# laser-jog-controller-0.net
KiCad netlist of a schematic drawn in EAGLE
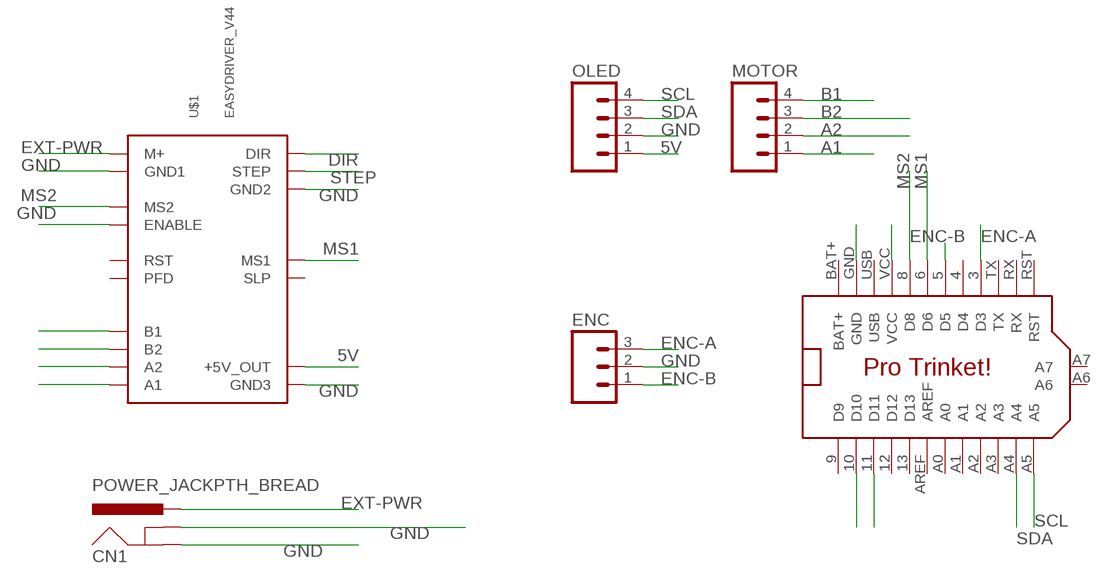
[diagram p0: schematic, sheet 1]

(export (version "E")
  (design (tool "Eeschema 10.0.6"))
  (components
    (comp (ref "CN1")
      (value "POWER_JACKPTH_BREAD")
      (footprint "eagle-import:POWER_JACK_PTH_BREAD")
      (libsource (lib "eagle-import") (part "POWER_JACKPTH_BREAD"))
    )
    (comp (ref "ENC")
      (value "M03LOCK_LONGPADS")
      (footprint "eagle-import:1X03_LOCK_LONGPADS")
      (libsource (lib "eagle-import") (part "M03LOCK_LONGPADS"))
    )
    (comp (ref "MOTOR")
      (value "M04LOCK_LONGPADS")
      (footprint "eagle-import:1X04_LOCK_LONGPADS")
      (libsource (lib "eagle-import") (part "M04LOCK_LONGPADS"))
    )
    (comp (ref "OLED")
      (value "M04LOCK_LONGPADS")
      (footprint "eagle-import:1X04_LOCK_LONGPADS")
      (libsource (lib "eagle-import") (part "M04LOCK_LONGPADS"))
    )
    (comp (ref "U$1")
      (value "EASYDRIVER_V44")
      (footprint "eagle-import:EASYDRIVER_V44")
      (libsource (lib "eagle-import") (part "EASYDRIVER_V44"))
    )
    (comp (ref "U$2")
      (value "PRO_TRINKET")
      (footprint "eagle-import:PROTRINKET")
      (libsource (lib "eagle-import") (part "PRO_TRINKET"))
    )
  )
  (nets
    (net (code "1") (name "/5V") (class "Default")
      (node (ref "OLED") (pin "1") (pinfunction "1_1") (pintype "passive"))
      (node (ref "U$1") (pin "P$11") (pinfunction "+5V_OUT_P$11") (pintype "bidirectional"))
      (node (ref "U$2") (pin "VCC") (pinfunction "VCC_VCC") (pintype "power_in"))
    )
    (net (code "2") (name "/A1") (class "Default")
      (node (ref "MOTOR") (pin "1") (pinfunction "1_1") (pintype "passive"))
      (node (ref "U$1") (pin "A1") (pinfunction "A1_A1") (pintype "bidirectional"))
    )
    (net (code "3") (name "/A2") (class "Default")
      (node (ref "MOTOR") (pin "2") (pinfunction "2_2") (pintype "passive"))
      (node (ref "U$1") (pin "A2") (pinfunction "A2_A2") (pintype "bidirectional"))
    )
    (net (code "4") (name "/B1") (class "Default")
      (node (ref "MOTOR") (pin "4") (pinfunction "4_4") (pintype "passive"))
      (node (ref "U$1") (pin "B1") (pinfunction "B1_B1") (pintype "bidirectional"))
    )
    (net (code "5") (name "/B2") (class "Default")
      (node (ref "MOTOR") (pin "3") (pinfunction "3_3") (pintype "passive"))
      (node (ref "U$1") (pin "B2") (pinfunction "B2_B2") (pintype "bidirectional"))
    )
    (net (code "6") (name "/BAT+") (class "Default")
      (node (ref "U$2") (pin "BAT+") (pinfunction "BAT+_BAT+") (pintype "power_in"))
    )
    (net (code "7") (name "/DIR") (class "Default")
      (node (ref "U$1") (pin "DIR") (pinfunction "DIR_DIR") (pintype "bidirectional"))
      (node (ref "U$2") (pin "11") (pinfunction "D11_11") (pintype "bidirectional"))
    )
    (net (code "8") (name "/ENC-A") (class "Default")
      (node (ref "ENC") (pin "3") (pinfunction "3_3") (pintype "passive"))
      (node (ref "U$2") (pin "3") (pinfunction "D3_3") (pintype "bidirectional"))
    )
    (net (code "9") (name "/ENC-B") (class "Default")
      (node (ref "ENC") (pin "1") (pinfunction "1_1") (pintype "passive"))
      (node (ref "U$2") (pin "5") (pinfunction "D5_5") (pintype "bidirectional"))
    )
    (net (code "10") (name "/EXT-PWR") (class "Default")
      (node (ref "CN1") (pin "PWR") (pinfunction "PWR_PWR") (pintype "bidirectional"))
      (node (ref "U$1") (pin "M+") (pinfunction "M+_M+") (pintype "bidirectional"))
    )
    (net (code "11") (name "/GND") (class "Default")
      (node (ref "CN1") (pin "GND") (pinfunction "GND_GND") (pintype "bidirectional"))
      (node (ref "CN1") (pin "GNDBREAK") (pinfunction "GNDBREAK_GNDBREAK") (pintype "bidirectional"))
      (node (ref "ENC") (pin "2") (pinfunction "2_2") (pintype "passive"))
      (node (ref "OLED") (pin "2") (pinfunction "2_2") (pintype "passive"))
      (node (ref "U$1") (pin "ENABLE") (pinfunction "ENABLE_ENABLE") (pintype "bidirectional"))
      (node (ref "U$1") (pin "GND1") (pinfunction "GND1_GND1") (pintype "bidirectional"))
      (node (ref "U$1") (pin "GND2") (pinfunction "GND2_GND2") (pintype "bidirectional"))
      (node (ref "U$1") (pin "GND3") (pinfunction "GND3_GND3") (pintype "bidirectional"))
      (node (ref "U$2") (pin "GND") (pinfunction "GND_GND") (pintype "power_in"))
    )
    (net (code "12") (name "/MS1") (class "Default")
      (node (ref "U$1") (pin "MS1") (pinfunction "MS1_MS1") (pintype "bidirectional"))
      (node (ref "U$2") (pin "6") (pinfunction "D6_6") (pintype "bidirectional"))
    )
    (net (code "13") (name "/MS2") (class "Default")
      (node (ref "U$1") (pin "MS2") (pinfunction "MS2_MS2") (pintype "bidirectional"))
      (node (ref "U$2") (pin "8") (pinfunction "D8_8") (pintype "bidirectional"))
    )
    (net (code "14") (name "/SCL") (class "Default")
      (node (ref "OLED") (pin "4") (pinfunction "4_4") (pintype "passive"))
      (node (ref "U$2") (pin "A5") (pinfunction "A5_A5") (pintype "bidirectional"))
    )
    (net (code "15") (name "/SDA") (class "Default")
      (node (ref "OLED") (pin "3") (pinfunction "3_3") (pintype "passive"))
      (node (ref "U$2") (pin "A4") (pinfunction "A4_A4") (pintype "bidirectional"))
    )
    (net (code "16") (name "/STEP") (class "Default")
      (node (ref "U$1") (pin "STEP") (pinfunction "STEP_STEP") (pintype "bidirectional"))
      (node (ref "U$2") (pin "10") (pinfunction "D10_10") (pintype "bidirectional"))
    )
    (net (code "17") (name "/USB") (class "Default")
      (node (ref "U$2") (pin "USB") (pinfunction "USB_USB") (pintype "power_in"))
    )
    (net (code "18") (name "unconnected-(U$1-PadPFD)") (class "Default")
      (node (ref "U$1") (pin "PFD") (pinfunction "PFD_PFD") (pintype "bidirectional"))
    )
    (net (code "19") (name "unconnected-(U$1-PadRST)") (class "Default")
      (node (ref "U$1") (pin "RST") (pinfunction "RST_RST") (pintype "bidirectional"))
    )
    (net (code "20") (name "unconnected-(U$1-SLP-PadSLEEP)") (class "Default")
      (node (ref "U$1") (pin "SLEEP") (pinfunction "SLP_SLEEP") (pintype "bidirectional"))
    )
    (net (code "21") (name "unconnected-(U$2-D4-Pad4)") (class "Default")
      (node (ref "U$2") (pin "4") (pinfunction "D4_4") (pintype "bidirectional"))
    )
    (net (code "22") (name "unconnected-(U$2-D9-Pad9)") (class "Default")
      (node (ref "U$2") (pin "9") (pinfunction "D9_9") (pintype "bidirectional"))
    )
    (net (code "23") (name "unconnected-(U$2-D12-Pad12)") (class "Default")
      (node (ref "U$2") (pin "12") (pinfunction "D12_12") (pintype "bidirectional"))
    )
    (net (code "24") (name "unconnected-(U$2-D13-Pad13)") (class "Default")
      (node (ref "U$2") (pin "13") (pinfunction "D13_13") (pintype "bidirectional"))
    )
    (net (code "25") (name "unconnected-(U$2-PadA0)") (class "Default")
      (node (ref "U$2") (pin "A0") (pinfunction "A0_A0") (pintype "bidirectional"))
    )
    (net (code "26") (name "unconnected-(U$2-PadA1)") (class "Default")
      (node (ref "U$2") (pin "A1") (pinfunction "A1_A1") (pintype "bidirectional"))
    )
    (net (code "27") (name "unconnected-(U$2-PadA2)") (class "Default")
      (node (ref "U$2") (pin "A2") (pinfunction "A2_A2") (pintype "bidirectional"))
    )
    (net (code "28") (name "unconnected-(U$2-PadA3)") (class "Default")
      (node (ref "U$2") (pin "A3") (pinfunction "A3_A3") (pintype "bidirectional"))
    )
    (net (code "29") (name "unconnected-(U$2-PadA6)") (class "Default")
      (node (ref "U$2") (pin "A6") (pinfunction "A6_A6") (pintype "passive"))
    )
    (net (code "30") (name "unconnected-(U$2-PadA7)") (class "Default")
      (node (ref "U$2") (pin "A7") (pinfunction "A7_A7") (pintype "passive"))
    )
    (net (code "31") (name "unconnected-(U$2-PadAREF)") (class "Default")
      (node (ref "U$2") (pin "AREF") (pinfunction "AREF_AREF") (pintype "passive"))
    )
    (net (code "32") (name "unconnected-(U$2-PadRST)") (class "Default")
      (node (ref "U$2") (pin "RST") (pinfunction "RST_RST") (pintype "passive"))
    )
    (net (code "33") (name "unconnected-(U$2-PadRX)") (class "Default")
      (node (ref "U$2") (pin "RX") (pinfunction "RX_RX") (pintype "bidirectional"))
    )
    (net (code "34") (name "unconnected-(U$2-PadTX)") (class "Default")
      (node (ref "U$2") (pin "TX") (pinfunction "TX_TX") (pintype "bidirectional"))
    )
  )
)
